# Hot_Water_Dispensar.net
KiCad netlist of a schematic drawn in Altium Designer
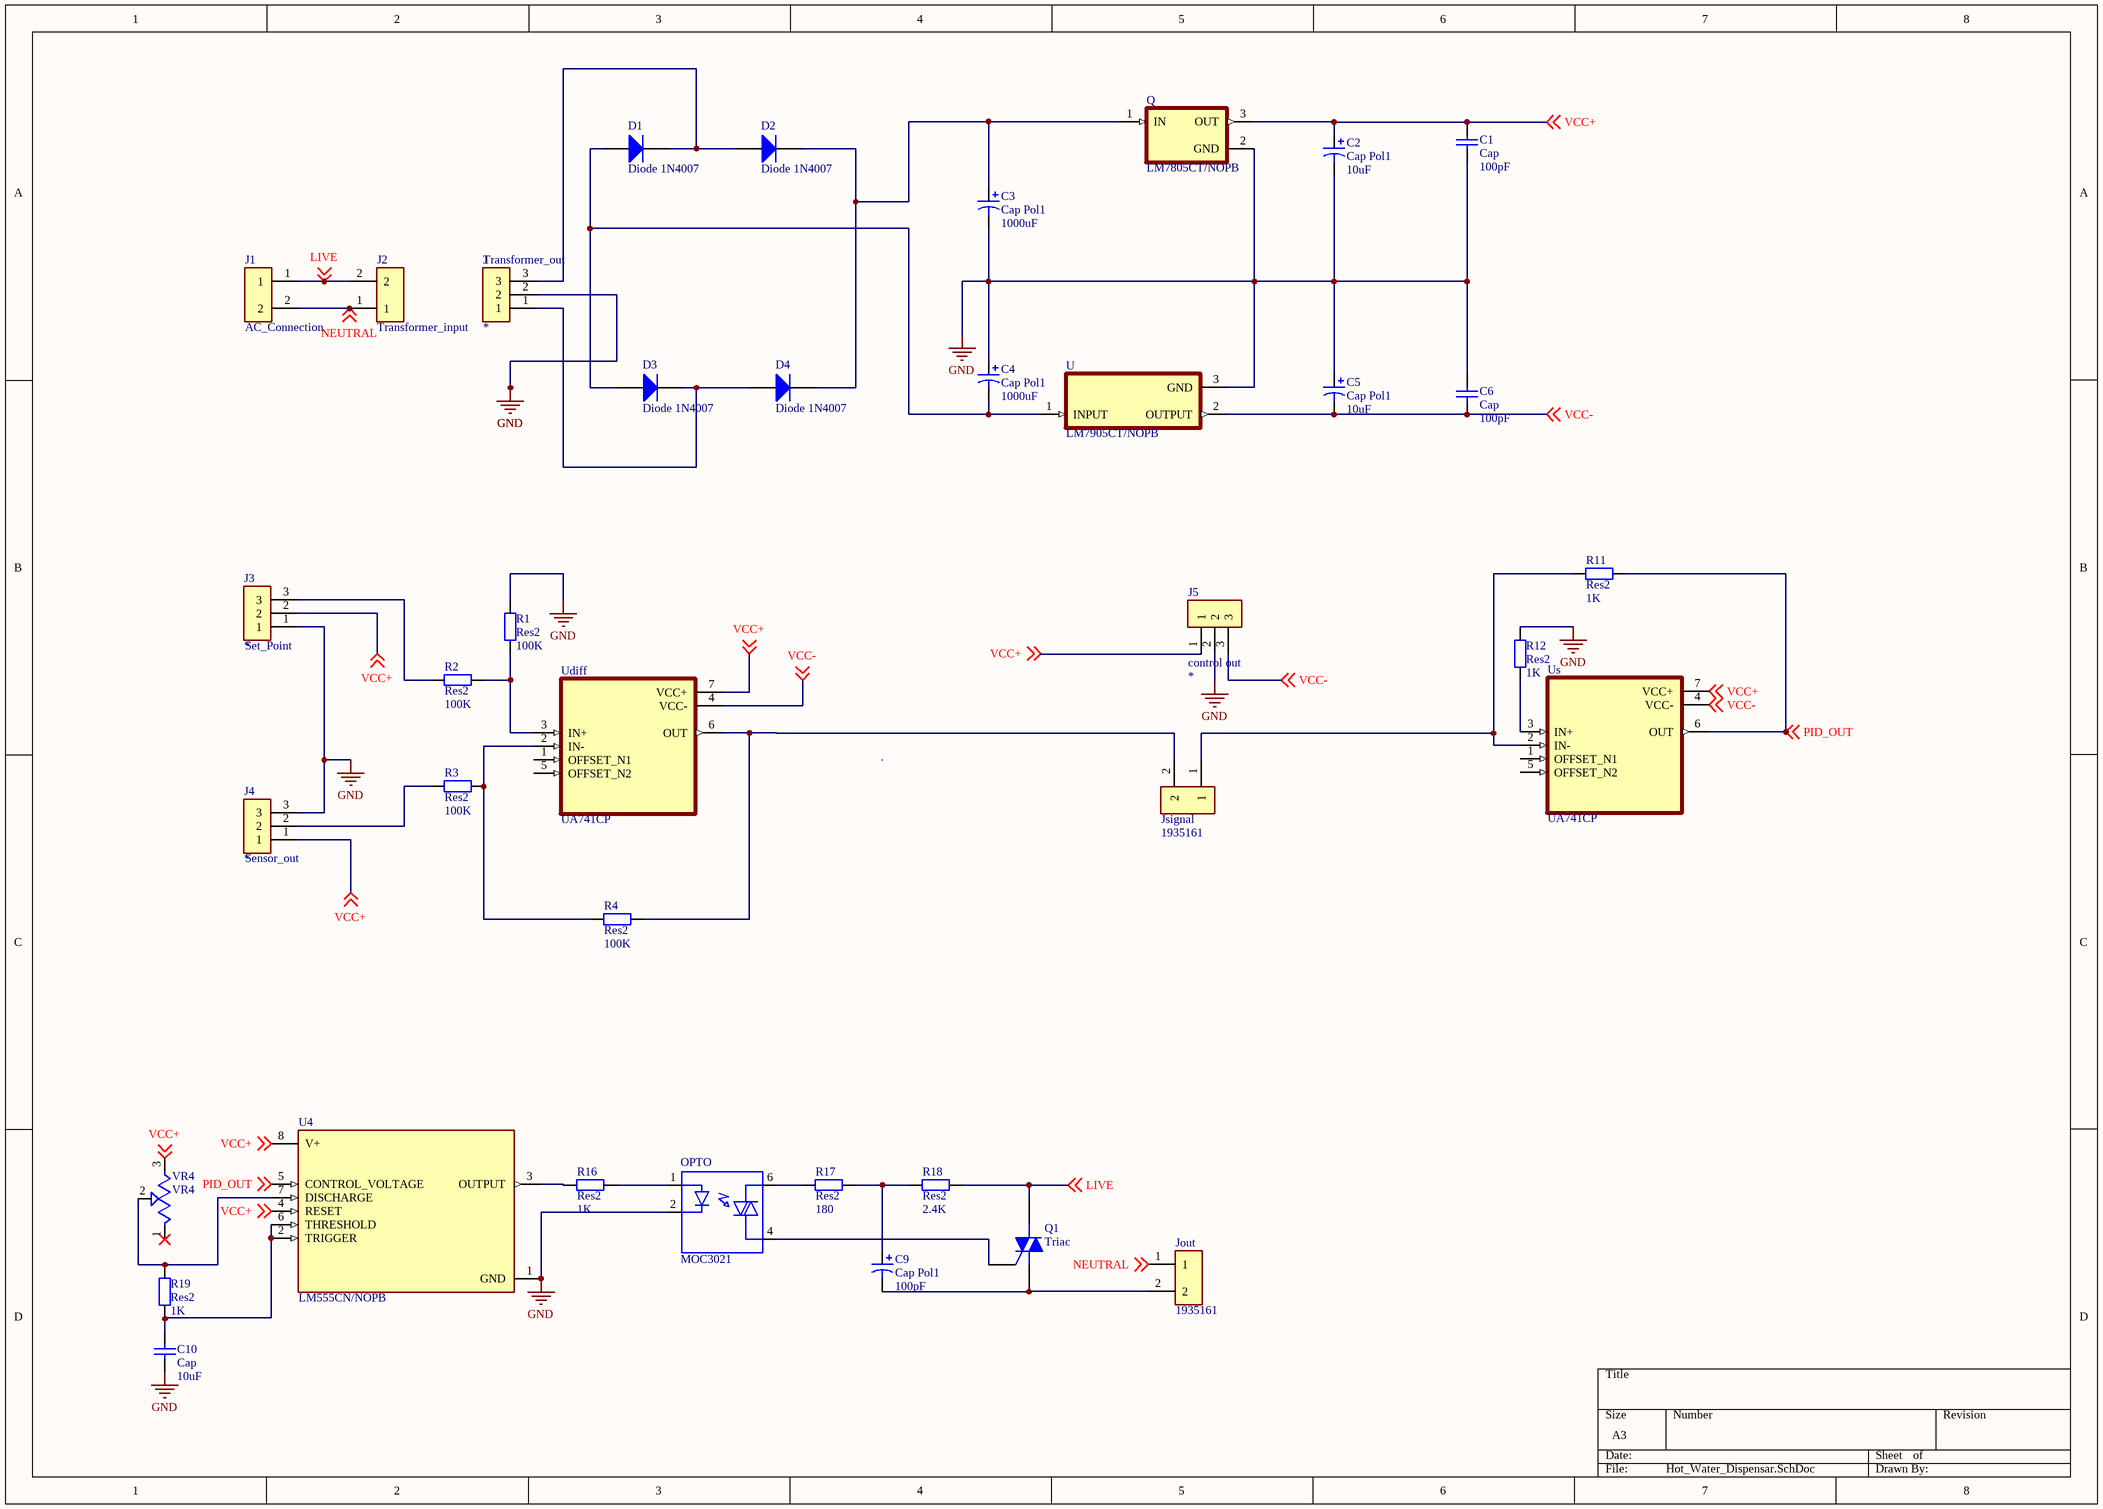
[diagram p0: Hot_Water_Dispensar.SchDoc]

(export (version "E")
  (design (tool "Eeschema 10.0.6"))
  (components
    (comp (ref "C1")
      (value "Cap")
      (footprint "RAD-0.3")
      (description "Capacitor")
      (fields (field (name "ALTIUM_VALUE") "100pF") (field (name "PUBLISHER") "Altium Limited"))
      (libsource (lib "Miscellaneous Devices") (part "Cap"))
    )
    (comp (ref "C2")
      (value "Cap Pol1")
      (footprint "RB7.6-15")
      (description "Polarized Capacitor (Radial)")
      (fields (field (name "ALTIUM_VALUE") "10uF") (field (name "PUBLISHER") "Altium Limited"))
      (libsource (lib "Miscellaneous Devices") (part "Cap Pol1"))
    )
    (comp (ref "C3")
      (value "Cap Pol1")
      (footprint "RB7.6-15")
      (description "Polarized Capacitor (Radial)")
      (fields (field (name "ALTIUM_VALUE") "1000uF") (field (name "PUBLISHER") "Altium Limited"))
      (libsource (lib "Miscellaneous Devices") (part "Cap Pol1"))
    )
    (comp (ref "C4")
      (value "Cap Pol1")
      (footprint "RB7.6-15")
      (description "Polarized Capacitor (Radial)")
      (fields (field (name "ALTIUM_VALUE") "1000uF") (field (name "PUBLISHER") "Altium Limited"))
      (libsource (lib "Miscellaneous Devices") (part "Cap Pol1"))
    )
    (comp (ref "C5")
      (value "Cap Pol1")
      (footprint "RB7.6-15")
      (description "Polarized Capacitor (Radial)")
      (fields (field (name "ALTIUM_VALUE") "10uF") (field (name "PUBLISHER") "Altium Limited"))
      (libsource (lib "Miscellaneous Devices") (part "Cap Pol1"))
    )
    (comp (ref "C6")
      (value "Cap")
      (footprint "RAD-0.3")
      (description "Capacitor")
      (fields (field (name "ALTIUM_VALUE") "100pF") (field (name "PUBLISHER") "Altium Limited"))
      (libsource (lib "Miscellaneous Devices") (part "Cap"))
    )
    (comp (ref "C9")
      (value "Cap Pol1")
      (footprint "RB7.6-15")
      (description "Polarized Capacitor (Radial)")
      (fields (field (name "ALTIUM_VALUE") "100pF") (field (name "PUBLISHER") "Altium Limited"))
      (libsource (lib "Miscellaneous Devices") (part "Cap Pol1"))
    )
    (comp (ref "C10")
      (value "Cap")
      (footprint "RAD-0.3")
      (description "Capacitor")
      (fields (field (name "ALTIUM_VALUE") "10uF") (field (name "PUBLISHER") "Altium Limited"))
      (libsource (lib "Miscellaneous Devices") (part "Cap"))
    )
    (comp (ref "D1")
      (value "Diode 1N4007")
      (footprint "DO-41")
      (description "1 Amp General Purpose Rectifier")
      (fields (field (name "PUBLISHER") "Altium Limited"))
      (libsource (lib "Miscellaneous Devices") (part "Diode 1N4007"))
    )
    (comp (ref "D2")
      (value "Diode 1N4007")
      (footprint "DO-41")
      (description "1 Amp General Purpose Rectifier")
      (fields (field (name "PUBLISHER") "Altium Limited"))
      (libsource (lib "Miscellaneous Devices") (part "Diode 1N4007"))
    )
    (comp (ref "D3")
      (value "Diode 1N4007")
      (footprint "DO-41")
      (description "1 Amp General Purpose Rectifier")
      (fields (field (name "PUBLISHER") "Altium Limited"))
      (libsource (lib "Miscellaneous Devices") (part "Diode 1N4007"))
    )
    (comp (ref "D4")
      (value "Diode 1N4007")
      (footprint "DO-41")
      (description "1 Amp General Purpose Rectifier")
      (fields (field (name "PUBLISHER") "Altium Limited"))
      (libsource (lib "Miscellaneous Devices") (part "Diode 1N4007"))
    )
    (comp (ref "J")
      (value "Transformer_out")
      (footprint "TE_282837-3")
      (description "Wire to Board 3 Position 5.08 mm Pitch 30-16 AWG Euro Style Terminal Block")
      (fields
        (field (name "MF") "TE Connectivity")
        (field (name "DIGI-KEY_PART_NUMBER") "A113321-ND")
        (field (name "COMMENT_1") "*")
      )
      (libsource (lib "282837-3") (part "282837-3"))
    )
    (comp (ref "J1")
      (value "AC_Connection")
      (footprint "PHOENIX_1935161")
      (description "2 Position Wire to Board Terminal Block Horizontal with Board 0.197 _5.00mm_ Through Hole")
      (fields (field (name "MP") "1935161") (field (name "MF") "Phoenix Contact"))
      (libsource (lib "") (part "1935161_1"))
    )
    (comp (ref "J2")
      (value "Transformer_input")
      (footprint "PHOENIX_1935161")
      (description "2 Position Wire to Board Terminal Block Horizontal with Board 0.197 _5.00mm_ Through Hole")
      (fields (field (name "MP") "1935161") (field (name "MF") "Phoenix Contact"))
      (libsource (lib "") (part "1935161_2"))
    )
    (comp (ref "J3")
      (value "Set_Point")
      (footprint "TE_282837-3")
      (description "Wire to Board 3 Position 5.08 mm Pitch 30-16 AWG Euro Style Terminal Block")
      (fields
        (field (name "MF") "TE Connectivity")
        (field (name "DIGI-KEY_PART_NUMBER") "A113321-ND")
        (field (name "COMMENT_1") "*")
      )
      (libsource (lib "282837-3") (part "282837-3"))
    )
    (comp (ref "J4")
      (value "Sensor_out")
      (footprint "TE_282837-3")
      (description "Wire to Board 3 Position 5.08 mm Pitch 30-16 AWG Euro Style Terminal Block")
      (fields
        (field (name "MF") "TE Connectivity")
        (field (name "DIGI-KEY_PART_NUMBER") "A113321-ND")
        (field (name "COMMENT_1") "*")
      )
      (libsource (lib "282837-3") (part "282837-3"))
    )
    (comp (ref "J5")
      (value "control out")
      (footprint "TE_282837-3")
      (description "Wire to Board 3 Position 5.08 mm Pitch 30-16 AWG Euro Style Terminal Block")
      (fields
        (field (name "MF") "TE Connectivity")
        (field (name "DIGI-KEY_PART_NUMBER") "A113321-ND")
        (field (name "COMMENT_1") "*")
      )
      (libsource (lib "") (part "282837-3_1"))
    )
    (comp (ref "Jout")
      (value "1935161")
      (footprint "PHOENIX_1935161")
      (description "2 Position Wire to Board Terminal Block Horizontal with Board 0.197 _5.00mm_ Through Hole")
      (fields (field (name "MF") "Phoenix Contact") (field (name "DIGI-KEY_PART_NUMBER") "277-1667-ND"))
      (libsource (lib "") (part "1935161_3"))
    )
    (comp (ref "Jsignal")
      (value "1935161")
      (footprint "PHOENIX_1935161")
      (description "2 Position Wire to Board Terminal Block Horizontal with Board 0.197 _5.00mm_ Through Hole")
      (fields (field (name "MF") "Phoenix Contact") (field (name "DIGI-KEY_PART_NUMBER") "277-1667-ND"))
      (libsource (lib "1935161 (1)") (part "1935161"))
    )
    (comp (ref "OPTO")
      (value "MOC3021")
      (footprint "DIP762W45P254L889H508Q6")
      (description "Optoisolator Triac Output 5000Vrms 1 Channel 6-DIP")
      (fields (field (name "MF") "Lite-On"))
      (libsource (lib "MOC3021") (part "MOC3021"))
    )
    (comp (ref "Q")
      (value "LM7805CT/NOPB")
      (footprint "TO254P1054X470X2600-3")
      (description "Linear Voltage Regulator IC 1 Output 1A TO-220-3")
      (fields (field (name "MP") "LM7805CT") (field (name "MF") "ON Semiconductor"))
      (libsource (lib "LM7805CT_NOPB") (part "LM7805CT/NOPB"))
    )
    (comp (ref "Q1")
      (value "Triac")
      (footprint "369-03")
      (description "Silicon Bidirectional Triode Thyristor")
      (fields (field (name "PUBLISHER") "Altium Limited"))
      (libsource (lib "Miscellaneous Devices") (part "Triac"))
    )
    (comp (ref "R1")
      (value "Res2")
      (footprint "AXIAL-0.4")
      (description "Resistor")
      (fields (field (name "ALTIUM_VALUE") "100K") (field (name "PUBLISHER") "Altium Limited"))
      (libsource (lib "") (part "Res2_1"))
    )
    (comp (ref "R2")
      (value "Res2")
      (footprint "AXIAL-0.4")
      (description "Resistor")
      (fields (field (name "ALTIUM_VALUE") "100K") (field (name "PUBLISHER") "Altium Limited"))
      (libsource (lib "Miscellaneous Devices") (part "Res2"))
    )
    (comp (ref "R3")
      (value "Res2")
      (footprint "AXIAL-0.4")
      (description "Resistor")
      (fields (field (name "ALTIUM_VALUE") "100K") (field (name "PUBLISHER") "Altium Limited"))
      (libsource (lib "Miscellaneous Devices") (part "Res2"))
    )
    (comp (ref "R4")
      (value "Res2")
      (footprint "AXIAL-0.4")
      (description "Resistor")
      (fields (field (name "ALTIUM_VALUE") "100K") (field (name "PUBLISHER") "Altium Limited"))
      (libsource (lib "Miscellaneous Devices") (part "Res2"))
    )
    (comp (ref "R11")
      (value "Res2")
      (footprint "AXIAL-0.4")
      (description "Resistor")
      (fields (field (name "ALTIUM_VALUE") "1K") (field (name "PUBLISHER") "Altium Limited"))
      (libsource (lib "") (part "Res2_2"))
    )
    (comp (ref "R12")
      (value "Res2")
      (footprint "AXIAL-0.4")
      (description "Resistor")
      (fields (field (name "ALTIUM_VALUE") "1K") (field (name "PUBLISHER") "Altium Limited"))
      (libsource (lib "") (part "Res2_1"))
    )
    (comp (ref "R16")
      (value "Res2")
      (footprint "AXIAL-0.4")
      (description "Resistor")
      (fields (field (name "ALTIUM_VALUE") "1K") (field (name "PUBLISHER") "Altium Limited"))
      (libsource (lib "Miscellaneous Devices") (part "Res2"))
    )
    (comp (ref "R17")
      (value "Res2")
      (footprint "AXIAL-0.4")
      (description "Resistor")
      (fields (field (name "ALTIUM_VALUE") "180") (field (name "PUBLISHER") "Altium Limited"))
      (libsource (lib "") (part "Res2_2"))
    )
    (comp (ref "R18")
      (value "Res2")
      (footprint "AXIAL-0.4")
      (description "Resistor")
      (fields (field (name "ALTIUM_VALUE") "2.4K") (field (name "PUBLISHER") "Altium Limited"))
      (libsource (lib "") (part "Res2_2"))
    )
    (comp (ref "R19")
      (value "Res2")
      (footprint "AXIAL-0.4")
      (description "Resistor")
      (fields (field (name "ALTIUM_VALUE") "1K") (field (name "PUBLISHER") "Altium Limited"))
      (libsource (lib "") (part "Res2_1"))
    )
    (comp (ref "U")
      (value "LM7905CT/NOPB")
      (footprint "TO254P1054X470X1955-3")
      (description "1.5-A, negative linear voltage regulator 3-TO-220 0 to 125")
      (fields (field (name "MF") "Texas Instruments"))
      (libsource (lib "LM7905CT_NOPB (1)") (part "LM7905CT/NOPB"))
    )
    (comp (ref "U4")
      (value "LM555CN/NOPB")
      (footprint "DIP794W45P254L959H508Q8")
      (libsource (lib "LM555CN_NOPB") (part "LM555CN/NOPB"))
    )
    (comp (ref "Udiff")
      (value "UA741CP")
      (footprint "DIP794W45P254L959H508Q8")
      (description "General-Purpose Operational Amplifier")
      (fields (field (name "MF") "Texas Instruments"))
      (libsource (lib "UA741CP") (part "UA741CP"))
    )
    (comp (ref "Us")
      (value "UA741CP")
      (footprint "DIP794W45P254L959H508Q8")
      (description "General-Purpose Operational Amplifier")
      (fields (field (name "MF") "Texas Instruments"))
      (libsource (lib "UA741CP") (part "UA741CP"))
    )
    (comp (ref "VR4")
      (value "VR4")
      (footprint "TRIM_3296W-1-100")
      (description "10 Ohms 0.5W, 1/2W PC Pins Through Hole Trimmer Potentiometer Cermet 25 Turn Top Adjustment")
      (fields (field (name "MP") "3296W-1-100") (field (name "MF") "Bourns"))
      (libsource (lib "3296W-1-100") (part "3296W-1-100"))
    )
  )
  (nets
    (net (code "1") (name "GND") (class "Default")
      (node (ref "C1") (pin "2") (pinfunction "2_2") (pintype "passive"))
      (node (ref "C10") (pin "1") (pinfunction "1_1") (pintype "passive"))
      (node (ref "C2") (pin "2") (pinfunction "2_2") (pintype "passive"))
      (node (ref "C3") (pin "2") (pinfunction "2_2") (pintype "passive"))
      (node (ref "C4") (pin "1") (pinfunction "1_1") (pintype "passive"))
      (node (ref "C5") (pin "1") (pinfunction "1_1") (pintype "passive"))
      (node (ref "C6") (pin "1") (pinfunction "1_1") (pintype "passive"))
      (node (ref "J") (pin "2") (pinfunction "2_2") (pintype "passive"))
      (node (ref "J3") (pin "1") (pinfunction "1_1") (pintype "passive"))
      (node (ref "J4") (pin "3") (pinfunction "3_3") (pintype "passive"))
      (node (ref "J5") (pin "2") (pinfunction "2_2") (pintype "passive"))
      (node (ref "OPTO") (pin "2") (pinfunction "CATODE_2") (pintype "passive"))
      (node (ref "Q") (pin "2") (pinfunction "GND_2") (pintype "power_in"))
      (node (ref "R1") (pin "2") (pinfunction "2_2") (pintype "passive"))
      (node (ref "R12") (pin "2") (pinfunction "2_2") (pintype "passive"))
      (node (ref "U") (pin "3") (pinfunction "GND_3") (pintype "power_in"))
      (node (ref "U4") (pin "1") (pinfunction "GND_1") (pintype "power_in"))
    )
    (net (code "2") (name "LIVE") (class "Default")
      (node (ref "J1") (pin "1") (pinfunction "1_1") (pintype "passive"))
      (node (ref "J2") (pin "2") (pinfunction "2_2") (pintype "passive"))
      (node (ref "Q1") (pin "2") (pinfunction "M2_2") (pintype "passive"))
      (node (ref "R18") (pin "1") (pinfunction "1_1") (pintype "passive"))
    )
    (net (code "3") (name "NEUTRAL") (class "Default")
      (node (ref "J1") (pin "2") (pinfunction "2_2") (pintype "passive"))
      (node (ref "J2") (pin "1") (pinfunction "1_1") (pintype "passive"))
      (node (ref "Jout") (pin "1") (pinfunction "1_1") (pintype "passive"))
    )
    (net (code "4") (name "Net-(C9-Pad1)") (class "Default")
      (node (ref "C9") (pin "1") (pinfunction "1_1") (pintype "passive"))
      (node (ref "R17") (pin "1") (pinfunction "1_1") (pintype "passive"))
      (node (ref "R18") (pin "2") (pinfunction "2_2") (pintype "passive"))
    )
    (net (code "5") (name "Net-(D1-A)") (class "Default")
      (node (ref "C4") (pin "2") (pinfunction "2_2") (pintype "passive"))
      (node (ref "D1") (pin "1") (pinfunction "A_1") (pintype "passive"))
      (node (ref "D3") (pin "1") (pinfunction "A_1") (pintype "passive"))
      (node (ref "U") (pin "1") (pinfunction "INPUT_1") (pintype "input"))
    )
    (net (code "6") (name "Net-(D1-K)") (class "Default")
      (node (ref "D1") (pin "2") (pinfunction "K_2") (pintype "passive"))
      (node (ref "D2") (pin "1") (pinfunction "A_1") (pintype "passive"))
      (node (ref "J") (pin "3") (pinfunction "3_3") (pintype "passive"))
    )
    (net (code "7") (name "Net-(D2-K)") (class "Default")
      (node (ref "C3") (pin "1") (pinfunction "1_1") (pintype "passive"))
      (node (ref "D2") (pin "2") (pinfunction "K_2") (pintype "passive"))
      (node (ref "D4") (pin "2") (pinfunction "K_2") (pintype "passive"))
      (node (ref "Q") (pin "1") (pinfunction "IN_1") (pintype "input"))
    )
    (net (code "8") (name "Net-(D3-K)") (class "Default")
      (node (ref "D3") (pin "2") (pinfunction "K_2") (pintype "passive"))
      (node (ref "D4") (pin "1") (pinfunction "A_1") (pintype "passive"))
      (node (ref "J") (pin "1") (pinfunction "1_1") (pintype "passive"))
    )
    (net (code "9") (name "Net-(J3-Pad3)") (class "Default")
      (node (ref "J3") (pin "3") (pinfunction "3_3") (pintype "passive"))
      (node (ref "R2") (pin "1") (pinfunction "1_1") (pintype "passive"))
    )
    (net (code "10") (name "Net-(J4-Pad2)") (class "Default")
      (node (ref "J4") (pin "2") (pinfunction "2_2") (pintype "passive"))
      (node (ref "R3") (pin "1") (pinfunction "1_1") (pintype "passive"))
    )
    (net (code "11") (name "Net-(OPTO-ANODE)") (class "Default")
      (node (ref "OPTO") (pin "1") (pinfunction "ANODE_1") (pintype "passive"))
      (node (ref "R16") (pin "2") (pinfunction "2_2") (pintype "passive"))
    )
    (net (code "12") (name "Net-(OPTO-MAIN_TERM1)") (class "Default")
      (node (ref "OPTO") (pin "6") (pinfunction "MAIN_TERM1_6") (pintype "passive"))
      (node (ref "R17") (pin "2") (pinfunction "2_2") (pintype "passive"))
    )
    (net (code "13") (name "Net-(OPTO-MAIN_TERM2)") (class "Default")
      (node (ref "OPTO") (pin "4") (pinfunction "MAIN_TERM2_4") (pintype "passive"))
      (node (ref "Q1") (pin "3") (pinfunction "G_3") (pintype "passive"))
    )
    (net (code "14") (name "Net-(Q1-M1)") (class "Default")
      (node (ref "C9") (pin "2") (pinfunction "2_2") (pintype "passive"))
      (node (ref "Jout") (pin "2") (pinfunction "2_2") (pintype "passive"))
      (node (ref "Q1") (pin "1") (pinfunction "M1_1") (pintype "passive"))
    )
    (net (code "15") (name "Net-(U4-DISCHARGE)") (class "Default")
      (node (ref "R19") (pin "2") (pinfunction "2_2") (pintype "passive"))
      (node (ref "U4") (pin "7") (pinfunction "DISCHARGE_7") (pintype "input"))
      (node (ref "VR4") (pin "2") (pinfunction "WIPER_2") (pintype "passive"))
    )
    (net (code "16") (name "Net-(U4-OUTPUT)") (class "Default")
      (node (ref "R16") (pin "1") (pinfunction "1_1") (pintype "passive"))
      (node (ref "U4") (pin "3") (pinfunction "OUTPUT_3") (pintype "output"))
    )
    (net (code "17") (name "Net-(U4-THRESHOLD)") (class "Default")
      (node (ref "C10") (pin "2") (pinfunction "2_2") (pintype "passive"))
      (node (ref "R19") (pin "1") (pinfunction "1_1") (pintype "passive"))
      (node (ref "U4") (pin "2") (pinfunction "TRIGGER_2") (pintype "input"))
      (node (ref "U4") (pin "6") (pinfunction "THRESHOLD_6") (pintype "input"))
    )
    (net (code "18") (name "Net-(Udiff-IN+)") (class "Default")
      (node (ref "R1") (pin "1") (pinfunction "1_1") (pintype "passive"))
      (node (ref "R2") (pin "2") (pinfunction "2_2") (pintype "passive"))
      (node (ref "Udiff") (pin "3") (pinfunction "IN+_3") (pintype "input"))
    )
    (net (code "19") (name "Net-(Udiff-IN-)") (class "Default")
      (node (ref "R3") (pin "2") (pinfunction "2_2") (pintype "passive"))
      (node (ref "R4") (pin "1") (pinfunction "1_1") (pintype "passive"))
      (node (ref "Udiff") (pin "2") (pinfunction "IN-_2") (pintype "input"))
    )
    (net (code "20") (name "Net-(Udiff-OUT)") (class "Default")
      (node (ref "Jsignal") (pin "2") (pinfunction "2_2") (pintype "passive"))
      (node (ref "R4") (pin "2") (pinfunction "2_2") (pintype "passive"))
      (node (ref "Udiff") (pin "6") (pinfunction "OUT_6") (pintype "output"))
    )
    (net (code "21") (name "Net-(Us-IN+)") (class "Default")
      (node (ref "R12") (pin "1") (pinfunction "1_1") (pintype "passive"))
      (node (ref "Us") (pin "3") (pinfunction "IN+_3") (pintype "input"))
    )
    (net (code "22") (name "Net-(Us-IN-)") (class "Default")
      (node (ref "Jsignal") (pin "1") (pinfunction "1_1") (pintype "passive"))
      (node (ref "R11") (pin "2") (pinfunction "2_2") (pintype "passive"))
      (node (ref "Us") (pin "2") (pinfunction "IN-_2") (pintype "input"))
    )
    (net (code "23") (name "PID_OUT") (class "Default")
      (node (ref "R11") (pin "1") (pinfunction "1_1") (pintype "passive"))
      (node (ref "U4") (pin "5") (pinfunction "CONTROL_VOLTAGE_5") (pintype "input"))
      (node (ref "Us") (pin "6") (pinfunction "OUT_6") (pintype "output"))
    )
    (net (code "24") (name "VCC+") (class "Default")
      (node (ref "C1") (pin "1") (pinfunction "1_1") (pintype "passive"))
      (node (ref "C2") (pin "1") (pinfunction "1_1") (pintype "passive"))
      (node (ref "J3") (pin "2") (pinfunction "2_2") (pintype "passive"))
      (node (ref "J4") (pin "1") (pinfunction "1_1") (pintype "passive"))
      (node (ref "J5") (pin "1") (pinfunction "1_1") (pintype "passive"))
      (node (ref "Q") (pin "3") (pinfunction "OUT_3") (pintype "output"))
      (node (ref "U4") (pin "4") (pinfunction "RESET_4") (pintype "input"))
      (node (ref "U4") (pin "8") (pinfunction "V+_8") (pintype "power_in"))
      (node (ref "Udiff") (pin "7") (pinfunction "VCC+_7") (pintype "power_in"))
      (node (ref "Us") (pin "7") (pinfunction "VCC+_7") (pintype "power_in"))
      (node (ref "VR4") (pin "3") (pinfunction "CW_3") (pintype "passive"))
    )
    (net (code "25") (name "VCC-") (class "Default")
      (node (ref "C5") (pin "2") (pinfunction "2_2") (pintype "passive"))
      (node (ref "C6") (pin "2") (pinfunction "2_2") (pintype "passive"))
      (node (ref "J5") (pin "3") (pinfunction "3_3") (pintype "passive"))
      (node (ref "U") (pin "2") (pinfunction "OUTPUT_2") (pintype "output"))
      (node (ref "Udiff") (pin "4") (pinfunction "VCC-_4") (pintype "power_in"))
      (node (ref "Us") (pin "4") (pinfunction "VCC-_4") (pintype "power_in"))
    )
    (net (code "26") (name "unconnected-(Udiff-OFFSET_N1-Pad1)") (class "Default")
      (node (ref "Udiff") (pin "1") (pinfunction "OFFSET_N1_1") (pintype "input"))
    )
    (net (code "27") (name "unconnected-(Udiff-OFFSET_N2-Pad5)") (class "Default")
      (node (ref "Udiff") (pin "5") (pinfunction "OFFSET_N2_5") (pintype "input"))
    )
    (net (code "28") (name "unconnected-(Us-OFFSET_N1-Pad1)") (class "Default")
      (node (ref "Us") (pin "1") (pinfunction "OFFSET_N1_1") (pintype "input"))
    )
    (net (code "29") (name "unconnected-(Us-OFFSET_N2-Pad5)") (class "Default")
      (node (ref "Us") (pin "5") (pinfunction "OFFSET_N2_5") (pintype "input"))
    )
    (net (code "30") (name "unconnected-(VR4-CCW-Pad1)") (class "Default")
      (node (ref "VR4") (pin "1") (pinfunction "CCW_1") (pintype "passive+no_connect"))
    )
  )
)
